# zinthesizer.net
KiCad netlist of a schematic drawn in EAGLE
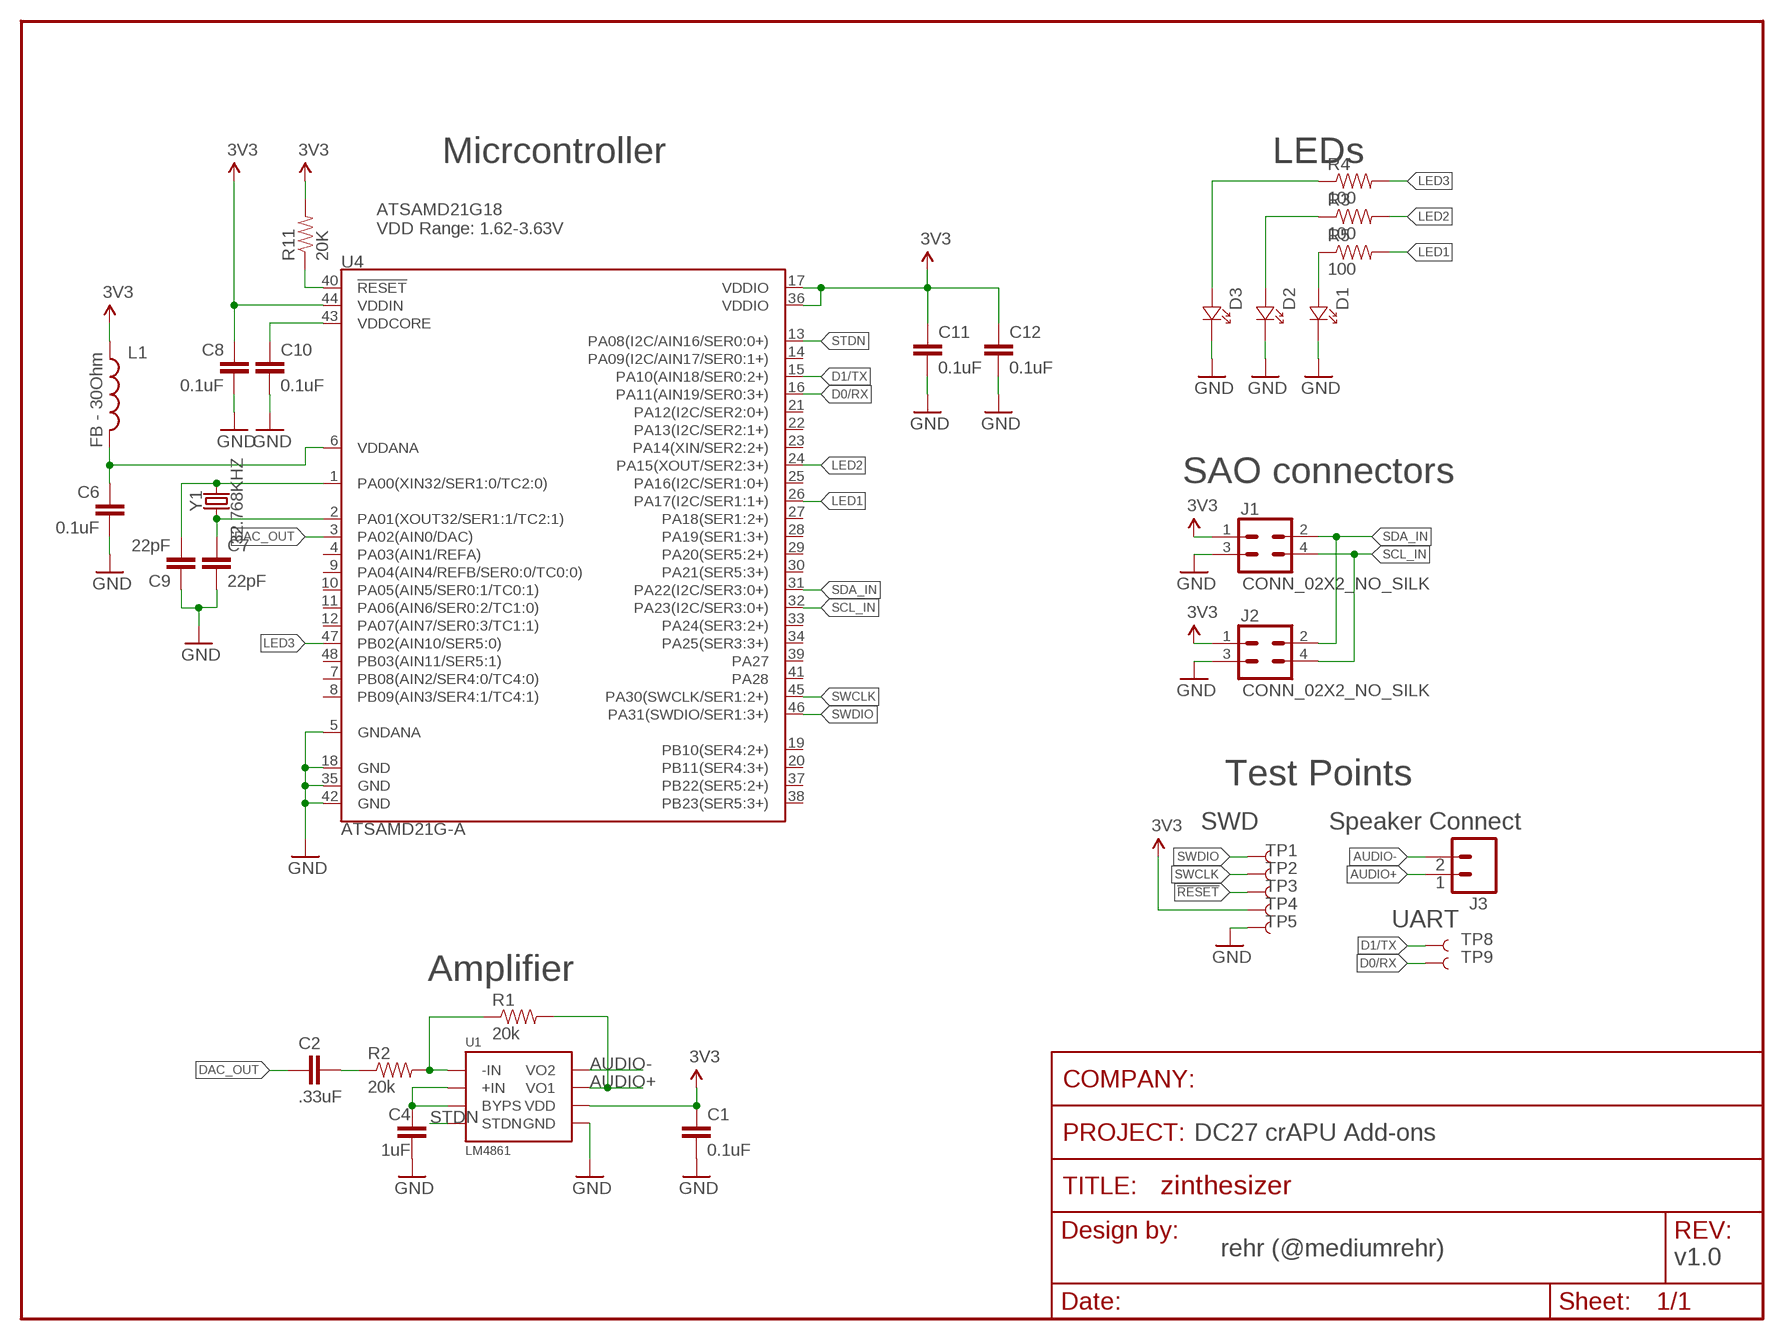
[diagram p0: schematic, sheet 1]

(export (version "E")
  (design (tool "Eeschema 10.0.6"))
  (components
    (comp (ref "C1")
      (value "0.1uF")
      (footprint "eagle-import:0603-CAP")
      (libsource (lib "eagle-import") (part "CAP0603-CAP"))
    )
    (comp (ref "C2")
      (value ".33uF")
      (footprint "eagle-import:0603-CAP")
      (libsource (lib "eagle-import") (part "CAP0603-CAP"))
    )
    (comp (ref "C4")
      (value "1uF")
      (footprint "eagle-import:0603-CAP")
      (libsource (lib "eagle-import") (part "CAP0603-CAP"))
    )
    (comp (ref "C6")
      (value "0.1uF")
      (footprint "eagle-import:0603-CAP")
      (libsource (lib "eagle-import") (part "0.1UF-25V(+80/-20%)(0603)"))
    )
    (comp (ref "C7")
      (value "22pF")
      (footprint "eagle-import:0603-CAP")
      (libsource (lib "eagle-import") (part "15PF-50V-5%(0603)"))
    )
    (comp (ref "C8")
      (value "0.1uF")
      (footprint "eagle-import:0603-CAP")
      (libsource (lib "eagle-import") (part "0.1UF-25V(+80/-20%)(0603)"))
    )
    (comp (ref "C9")
      (value "22pF")
      (footprint "eagle-import:0603-CAP")
      (libsource (lib "eagle-import") (part "15PF-50V-5%(0603)"))
    )
    (comp (ref "C10")
      (value "0.1uF")
      (footprint "eagle-import:0603-CAP")
      (libsource (lib "eagle-import") (part "0.1UF-25V(+80/-20%)(0603)"))
    )
    (comp (ref "C11")
      (value "0.1uF")
      (footprint "eagle-import:0603-CAP")
      (libsource (lib "eagle-import") (part "0.1UF-25V(+80/-20%)(0603)"))
    )
    (comp (ref "C12")
      (value "0.1uF")
      (footprint "eagle-import:0603-CAP")
      (libsource (lib "eagle-import") (part "0.1UF-25V(+80/-20%)(0603)"))
    )
    (comp (ref "D1")
      (value "LED1206REVERSE_NO_SILK")
      (footprint "eagle-import:1206_NO_SILK")
      (libsource (lib "eagle-import") (part "LED1206REVERSE_NO_SILK"))
    )
    (comp (ref "D2")
      (value "LED1206REVERSE_NO_SILK")
      (footprint "eagle-import:1206_NO_SILK")
      (libsource (lib "eagle-import") (part "LED1206REVERSE_NO_SILK"))
    )
    (comp (ref "D3")
      (value "LED1206REVERSE_NO_SILK")
      (footprint "eagle-import:1206_NO_SILK")
      (libsource (lib "eagle-import") (part "LED1206REVERSE_NO_SILK"))
    )
    (comp (ref "FRAME1")
      (value "FRAME-LETTER-BLANKNO_PACKAGE")
      (footprint "eagle-import:DUMMY")
      (fields (field (name "DESIGNER") "Nobody"))
      (libsource (lib "eagle-import") (part "FRAME-LETTER-BLANKNO_PACKAGE"))
    )
    (comp (ref "J1")
      (value "CONN_02X2_NO_SILK")
      (footprint "eagle-import:2X2_NO_SILK")
      (libsource (lib "eagle-import") (part "CONN_02X2_NO_SILK"))
    )
    (comp (ref "J2")
      (value "CONN_02X2_NO_SILK")
      (footprint "eagle-import:2X2_NO_SILK")
      (libsource (lib "eagle-import") (part "CONN_02X2_NO_SILK"))
    )
    (comp (ref "J3")
      (value "M02ROUND")
      (footprint "eagle-import:M02_ROUND")
      (libsource (lib "eagle-import") (part "M02ROUND"))
    )
    (comp (ref "L1")
      (value "FB - 30Ohm")
      (footprint "eagle-import:0603")
      (libsource (lib "eagle-import") (part "INDUCTOR0603"))
    )
    (comp (ref "R1")
      (value "20k")
      (footprint "eagle-import:0805")
      (libsource (lib "eagle-import") (part "RESISTOR0805-RES"))
    )
    (comp (ref "R2")
      (value "20k")
      (footprint "eagle-import:0805")
      (libsource (lib "eagle-import") (part "RESISTOR0805-RES"))
    )
    (comp (ref "R3")
      (value "100")
      (footprint "eagle-import:0603-RES")
      (libsource (lib "eagle-import") (part "10KOHM-1/10W-1%(0603)0603"))
    )
    (comp (ref "R4")
      (value "100")
      (footprint "eagle-import:0603-RES")
      (libsource (lib "eagle-import") (part "10KOHM-1/10W-1%(0603)0603"))
    )
    (comp (ref "R5")
      (value "100")
      (footprint "eagle-import:0603-RES")
      (libsource (lib "eagle-import") (part "10KOHM-1/10W-1%(0603)0603"))
    )
    (comp (ref "R11")
      (value "20K")
      (footprint "eagle-import:0603-RES")
      (libsource (lib "eagle-import") (part "10KOHM-1/10W-1%(0603)0603"))
    )
    (comp (ref "TP1")
      (value "TEST-POINT3X5")
      (footprint "eagle-import:PAD.03X.05")
      (libsource (lib "eagle-import") (part "TEST-POINT3X5"))
    )
    (comp (ref "TP2")
      (value "TEST-POINT3X5")
      (footprint "eagle-import:PAD.03X.05")
      (libsource (lib "eagle-import") (part "TEST-POINT3X5"))
    )
    (comp (ref "TP3")
      (value "TEST-POINT3X5")
      (footprint "eagle-import:PAD.03X.05")
      (libsource (lib "eagle-import") (part "TEST-POINT3X5"))
    )
    (comp (ref "TP4")
      (value "TEST-POINT3X5")
      (footprint "eagle-import:PAD.03X.05")
      (libsource (lib "eagle-import") (part "TEST-POINT3X5"))
    )
    (comp (ref "TP5")
      (value "TEST-POINT3X5")
      (footprint "eagle-import:PAD.03X.05")
      (libsource (lib "eagle-import") (part "TEST-POINT3X5"))
    )
    (comp (ref "TP8")
      (value "TEST-POINT3X4")
      (footprint "eagle-import:PAD.03X.04")
      (libsource (lib "eagle-import") (part "TEST-POINT3X4"))
    )
    (comp (ref "TP9")
      (value "TEST-POINT3X4")
      (footprint "eagle-import:PAD.03X.04")
      (libsource (lib "eagle-import") (part "TEST-POINT3X4"))
    )
    (comp (ref "U1")
      (value "LM4861")
      (footprint "eagle-import:8-SOIC")
      (libsource (lib "eagle-import") (part "LM4861"))
    )
    (comp (ref "U4")
      (value "ATSAMD21G-A")
      (footprint "eagle-import:TQFP-48")
      (libsource (lib "eagle-import") (part "ATSAMD21G-A"))
    )
    (comp (ref "Y1")
      (value "32.768KHZ")
      (footprint "eagle-import:ABS06")
      (libsource (lib "eagle-import") (part "ABS06-127-32.768KHZ"))
    )
  )
  (nets
    (net (code "1") (name "/~{RESET}") (class "Default")
      (node (ref "R11") (pin "1") (pinfunction "1_1") (pintype "passive"))
      (node (ref "TP3") (pin "P$1") (pinfunction "1_P$1") (pintype "bidirectional"))
      (node (ref "U4") (pin "40") (pinfunction "~{RESET}_40") (pintype "bidirectional"))
    )
    (net (code "2") (name "3V3") (class "Default")
      (node (ref "C1") (pin "1") (pinfunction "1_1") (pintype "passive"))
      (node (ref "C11") (pin "1") (pinfunction "1_1") (pintype "passive"))
      (node (ref "C12") (pin "1") (pinfunction "1_1") (pintype "passive"))
      (node (ref "C8") (pin "1") (pinfunction "1_1") (pintype "passive"))
      (node (ref "J1") (pin "1") (pinfunction "1_1") (pintype "bidirectional"))
      (node (ref "J2") (pin "1") (pinfunction "1_1") (pintype "bidirectional"))
      (node (ref "L1") (pin "1") (pinfunction "1_1") (pintype "passive"))
      (node (ref "R11") (pin "2") (pinfunction "2_2") (pintype "passive"))
      (node (ref "TP4") (pin "P$1") (pinfunction "1_P$1") (pintype "bidirectional"))
      (node (ref "U1") (pin "P$6") (pinfunction "VDD_P$6") (pintype "bidirectional"))
      (node (ref "U4") (pin "17") (pinfunction "VDDIO_17") (pintype "bidirectional"))
      (node (ref "U4") (pin "36") (pinfunction "VDDIO_36") (pintype "bidirectional"))
      (node (ref "U4") (pin "44") (pinfunction "VDDIN_44") (pintype "bidirectional"))
    )
    (net (code "3") (name "AUDIO+") (class "Default")
      (node (ref "J3") (pin "P$1") (pinfunction "P$1_P$1") (pintype "bidirectional"))
      (node (ref "R1") (pin "2") (pinfunction "2_2") (pintype "passive"))
      (node (ref "U1") (pin "P$5") (pinfunction "VO1_P$5") (pintype "bidirectional"))
    )
    (net (code "4") (name "AUDIO-") (class "Default")
      (node (ref "J3") (pin "P$2") (pinfunction "P$2_P$2") (pintype "bidirectional"))
      (node (ref "U1") (pin "P$8") (pinfunction "VO2_P$8") (pintype "bidirectional"))
    )
    (net (code "5") (name "D0{slash}RX") (class "Default")
      (node (ref "TP9") (pin "P$1") (pinfunction "1_P$1") (pintype "bidirectional"))
      (node (ref "U4") (pin "16") (pinfunction "PA11(AIN19/SER0:3+)_16") (pintype "bidirectional"))
    )
    (net (code "6") (name "D1{slash}TX") (class "Default")
      (node (ref "TP8") (pin "P$1") (pinfunction "1_P$1") (pintype "bidirectional"))
      (node (ref "U4") (pin "15") (pinfunction "PA10(AIN18/SER0:2+)_15") (pintype "bidirectional"))
    )
    (net (code "7") (name "DAC_OUT") (class "Default")
      (node (ref "C2") (pin "2") (pinfunction "2_2") (pintype "passive"))
      (node (ref "U4") (pin "3") (pinfunction "PA02(AIN0/DAC)_3") (pintype "bidirectional"))
    )
    (net (code "8") (name "GND") (class "Default")
      (node (ref "C1") (pin "2") (pinfunction "2_2") (pintype "passive"))
      (node (ref "C10") (pin "2") (pinfunction "2_2") (pintype "passive"))
      (node (ref "C11") (pin "2") (pinfunction "2_2") (pintype "passive"))
      (node (ref "C12") (pin "2") (pinfunction "2_2") (pintype "passive"))
      (node (ref "C4") (pin "2") (pinfunction "2_2") (pintype "passive"))
      (node (ref "C6") (pin "2") (pinfunction "2_2") (pintype "passive"))
      (node (ref "C7") (pin "2") (pinfunction "2_2") (pintype "passive"))
      (node (ref "C8") (pin "2") (pinfunction "2_2") (pintype "passive"))
      (node (ref "C9") (pin "1") (pinfunction "1_1") (pintype "passive"))
      (node (ref "D1") (pin "P$1") (pinfunction "P$2_P$1") (pintype "bidirectional"))
      (node (ref "D2") (pin "P$1") (pinfunction "P$2_P$1") (pintype "bidirectional"))
      (node (ref "D3") (pin "P$1") (pinfunction "P$2_P$1") (pintype "bidirectional"))
      (node (ref "J1") (pin "3") (pinfunction "3_3") (pintype "bidirectional"))
      (node (ref "J2") (pin "3") (pinfunction "3_3") (pintype "bidirectional"))
      (node (ref "TP5") (pin "P$1") (pinfunction "1_P$1") (pintype "bidirectional"))
      (node (ref "U1") (pin "P$7") (pinfunction "GND_P$7") (pintype "bidirectional"))
      (node (ref "U4") (pin "18") (pinfunction "GND_18") (pintype "bidirectional"))
      (node (ref "U4") (pin "35") (pinfunction "GND_35") (pintype "bidirectional"))
      (node (ref "U4") (pin "42") (pinfunction "GND_42") (pintype "bidirectional"))
      (node (ref "U4") (pin "5") (pinfunction "GNDANA_5") (pintype "bidirectional"))
    )
    (net (code "9") (name "LED1") (class "Default")
      (node (ref "R5") (pin "2") (pinfunction "2_2") (pintype "passive"))
      (node (ref "U4") (pin "26") (pinfunction "PA17(I2C/SER1:1+)_26") (pintype "bidirectional"))
    )
    (net (code "10") (name "LED2") (class "Default")
      (node (ref "R3") (pin "2") (pinfunction "2_2") (pintype "passive"))
      (node (ref "U4") (pin "24") (pinfunction "PA15(XOUT/SER2:3+)_24") (pintype "bidirectional"))
    )
    (net (code "11") (name "LED3") (class "Default")
      (node (ref "R4") (pin "2") (pinfunction "2_2") (pintype "passive"))
      (node (ref "U4") (pin "47") (pinfunction "PB02(AIN10/SER5:0)_47") (pintype "bidirectional"))
    )
    (net (code "12") (name "Net-(C2-Pad1)") (class "Default")
      (node (ref "C2") (pin "1") (pinfunction "1_1") (pintype "passive"))
      (node (ref "R2") (pin "1") (pinfunction "1_1") (pintype "passive"))
    )
    (net (code "13") (name "Net-(D1-P$1)") (class "Default")
      (node (ref "D1") (pin "P$2") (pinfunction "P$1_P$2") (pintype "bidirectional"))
      (node (ref "R5") (pin "1") (pinfunction "1_1") (pintype "passive"))
    )
    (net (code "14") (name "Net-(D2-P$1)") (class "Default")
      (node (ref "D2") (pin "P$2") (pinfunction "P$1_P$2") (pintype "bidirectional"))
      (node (ref "R3") (pin "1") (pinfunction "1_1") (pintype "passive"))
    )
    (net (code "15") (name "Net-(D3-P$1)") (class "Default")
      (node (ref "D3") (pin "P$2") (pinfunction "P$1_P$2") (pintype "bidirectional"))
      (node (ref "R4") (pin "1") (pinfunction "1_1") (pintype "passive"))
    )
    (net (code "16") (name "Net-(U1-+IN)") (class "Default")
      (node (ref "C4") (pin "1") (pinfunction "1_1") (pintype "passive"))
      (node (ref "U1") (pin "P$2") (pinfunction "BYPS_P$2") (pintype "bidirectional"))
      (node (ref "U1") (pin "P$3") (pinfunction "+IN_P$3") (pintype "bidirectional"))
    )
    (net (code "17") (name "Net-(U1--IN)") (class "Default")
      (node (ref "R1") (pin "1") (pinfunction "1_1") (pintype "passive"))
      (node (ref "R2") (pin "2") (pinfunction "2_2") (pintype "passive"))
      (node (ref "U1") (pin "P$4") (pinfunction "-IN_P$4") (pintype "bidirectional"))
    )
    (net (code "18") (name "Net-(U4-PA00(XIN32{slash}SER1:0{slash}TC2:0))") (class "Default")
      (node (ref "C9") (pin "2") (pinfunction "2_2") (pintype "passive"))
      (node (ref "U4") (pin "1") (pinfunction "PA00(XIN32/SER1:0/TC2:0)_1") (pintype "bidirectional"))
      (node (ref "Y1") (pin "P$2") (pinfunction "2_P$2") (pintype "passive"))
    )
    (net (code "19") (name "Net-(U4-PA01(XOUT32{slash}SER1:1{slash}TC2:1))") (class "Default")
      (node (ref "C7") (pin "1") (pinfunction "1_1") (pintype "passive"))
      (node (ref "U4") (pin "2") (pinfunction "PA01(XOUT32/SER1:1/TC2:1)_2") (pintype "bidirectional"))
      (node (ref "Y1") (pin "P$1") (pinfunction "1_P$1") (pintype "passive"))
    )
    (net (code "20") (name "Net-(U4-VDDANA)") (class "Default")
      (node (ref "C6") (pin "1") (pinfunction "1_1") (pintype "passive"))
      (node (ref "L1") (pin "2") (pinfunction "2_2") (pintype "passive"))
      (node (ref "U4") (pin "6") (pinfunction "VDDANA_6") (pintype "bidirectional"))
    )
    (net (code "21") (name "Net-(U4-VDDCORE)") (class "Default")
      (node (ref "C10") (pin "1") (pinfunction "1_1") (pintype "passive"))
      (node (ref "U4") (pin "43") (pinfunction "VDDCORE_43") (pintype "bidirectional"))
    )
    (net (code "22") (name "SCL_IN") (class "Default")
      (node (ref "J1") (pin "4") (pinfunction "4_4") (pintype "bidirectional"))
      (node (ref "J2") (pin "4") (pinfunction "4_4") (pintype "bidirectional"))
      (node (ref "U4") (pin "32") (pinfunction "PA23(I2C/SER3:0+)_32") (pintype "bidirectional"))
    )
    (net (code "23") (name "SDA_IN") (class "Default")
      (node (ref "J1") (pin "2") (pinfunction "2_2") (pintype "bidirectional"))
      (node (ref "J2") (pin "2") (pinfunction "2_2") (pintype "bidirectional"))
      (node (ref "U4") (pin "31") (pinfunction "PA22(I2C/SER3:0+)_31") (pintype "bidirectional"))
    )
    (net (code "24") (name "STDN") (class "Default")
      (node (ref "U1") (pin "P$1") (pinfunction "STDN_P$1") (pintype "bidirectional"))
      (node (ref "U4") (pin "13") (pinfunction "PA08(I2C/AIN16/SER0:0+)_13") (pintype "bidirectional"))
    )
    (net (code "25") (name "SWCLK") (class "Default")
      (node (ref "TP2") (pin "P$1") (pinfunction "1_P$1") (pintype "bidirectional"))
      (node (ref "U4") (pin "45") (pinfunction "PA30(SWCLK/SER1:2+)_45") (pintype "bidirectional"))
    )
    (net (code "26") (name "SWDIO") (class "Default")
      (node (ref "TP1") (pin "P$1") (pinfunction "1_P$1") (pintype "bidirectional"))
      (node (ref "U4") (pin "46") (pinfunction "PA31(SWDIO/SER1:3+)_46") (pintype "bidirectional"))
    )
    (net (code "27") (name "unconnected-(U4-PA03(AIN1{slash}REFA)-Pad4)") (class "Default")
      (node (ref "U4") (pin "4") (pinfunction "PA03(AIN1/REFA)_4") (pintype "bidirectional"))
    )
    (net (code "28") (name "unconnected-(U4-PA04(AIN4{slash}REFB{slash}SER0:0{slash}TC0:0)-Pad9)") (class "Default")
      (node (ref "U4") (pin "9") (pinfunction "PA04(AIN4/REFB/SER0:0/TC0:0)_9") (pintype "bidirectional"))
    )
    (net (code "29") (name "unconnected-(U4-PA05(AIN5{slash}SER0:1{slash}TC0:1)-Pad10)") (class "Default")
      (node (ref "U4") (pin "10") (pinfunction "PA05(AIN5/SER0:1/TC0:1)_10") (pintype "bidirectional"))
    )
    (net (code "30") (name "unconnected-(U4-PA06(AIN6{slash}SER0:2{slash}TC1:0)-Pad11)") (class "Default")
      (node (ref "U4") (pin "11") (pinfunction "PA06(AIN6/SER0:2/TC1:0)_11") (pintype "bidirectional"))
    )
    (net (code "31") (name "unconnected-(U4-PA07(AIN7{slash}SER0:3{slash}TC1:1)-Pad12)") (class "Default")
      (node (ref "U4") (pin "12") (pinfunction "PA07(AIN7/SER0:3/TC1:1)_12") (pintype "bidirectional"))
    )
    (net (code "32") (name "unconnected-(U4-PA09(I2C{slash}AIN17{slash}SER0:1+)-Pad14)") (class "Default")
      (node (ref "U4") (pin "14") (pinfunction "PA09(I2C/AIN17/SER0:1+)_14") (pintype "bidirectional"))
    )
    (net (code "33") (name "unconnected-(U4-PA12(I2C{slash}SER2:0+)-Pad21)") (class "Default")
      (node (ref "U4") (pin "21") (pinfunction "PA12(I2C/SER2:0+)_21") (pintype "bidirectional"))
    )
    (net (code "34") (name "unconnected-(U4-PA13(I2C{slash}SER2:1+)-Pad22)") (class "Default")
      (node (ref "U4") (pin "22") (pinfunction "PA13(I2C/SER2:1+)_22") (pintype "bidirectional"))
    )
    (net (code "35") (name "unconnected-(U4-PA14(XIN{slash}SER2:2+)-Pad23)") (class "Default")
      (node (ref "U4") (pin "23") (pinfunction "PA14(XIN/SER2:2+)_23") (pintype "bidirectional"))
    )
    (net (code "36") (name "unconnected-(U4-PA16(I2C{slash}SER1:0+)-Pad25)") (class "Default")
      (node (ref "U4") (pin "25") (pinfunction "PA16(I2C/SER1:0+)_25") (pintype "bidirectional"))
    )
    (net (code "37") (name "unconnected-(U4-PA18(SER1:2+)-Pad27)") (class "Default")
      (node (ref "U4") (pin "27") (pinfunction "PA18(SER1:2+)_27") (pintype "bidirectional"))
    )
    (net (code "38") (name "unconnected-(U4-PA19(SER1:3+)-Pad28)") (class "Default")
      (node (ref "U4") (pin "28") (pinfunction "PA19(SER1:3+)_28") (pintype "bidirectional"))
    )
    (net (code "39") (name "unconnected-(U4-PA20(SER5:2+)-Pad29)") (class "Default")
      (node (ref "U4") (pin "29") (pinfunction "PA20(SER5:2+)_29") (pintype "bidirectional"))
    )
    (net (code "40") (name "unconnected-(U4-PA21(SER5:3+)-Pad30)") (class "Default")
      (node (ref "U4") (pin "30") (pinfunction "PA21(SER5:3+)_30") (pintype "bidirectional"))
    )
    (net (code "41") (name "unconnected-(U4-PA24(SER3:2+)-Pad33)") (class "Default")
      (node (ref "U4") (pin "33") (pinfunction "PA24(SER3:2+)_33") (pintype "bidirectional"))
    )
    (net (code "42") (name "unconnected-(U4-PA25(SER3:3+)-Pad34)") (class "Default")
      (node (ref "U4") (pin "34") (pinfunction "PA25(SER3:3+)_34") (pintype "bidirectional"))
    )
    (net (code "43") (name "unconnected-(U4-PA27-Pad39)") (class "Default")
      (node (ref "U4") (pin "39") (pinfunction "PA27_39") (pintype "bidirectional"))
    )
    (net (code "44") (name "unconnected-(U4-PA28-Pad41)") (class "Default")
      (node (ref "U4") (pin "41") (pinfunction "PA28_41") (pintype "bidirectional"))
    )
    (net (code "45") (name "unconnected-(U4-PB03(AIN11{slash}SER5:1)-Pad48)") (class "Default")
      (node (ref "U4") (pin "48") (pinfunction "PB03(AIN11/SER5:1)_48") (pintype "bidirectional"))
    )
    (net (code "46") (name "unconnected-(U4-PB08(AIN2{slash}SER4:0{slash}TC4:0)-Pad7)") (class "Default")
      (node (ref "U4") (pin "7") (pinfunction "PB08(AIN2/SER4:0/TC4:0)_7") (pintype "bidirectional"))
    )
    (net (code "47") (name "unconnected-(U4-PB09(AIN3{slash}SER4:1{slash}TC4:1)-Pad8)") (class "Default")
      (node (ref "U4") (pin "8") (pinfunction "PB09(AIN3/SER4:1/TC4:1)_8") (pintype "bidirectional"))
    )
    (net (code "48") (name "unconnected-(U4-PB10(SER4:2+)-Pad19)") (class "Default")
      (node (ref "U4") (pin "19") (pinfunction "PB10(SER4:2+)_19") (pintype "bidirectional"))
    )
    (net (code "49") (name "unconnected-(U4-PB11(SER4:3+)-Pad20)") (class "Default")
      (node (ref "U4") (pin "20") (pinfunction "PB11(SER4:3+)_20") (pintype "bidirectional"))
    )
    (net (code "50") (name "unconnected-(U4-PB22(SER5:2+)-Pad37)") (class "Default")
      (node (ref "U4") (pin "37") (pinfunction "PB22(SER5:2+)_37") (pintype "bidirectional"))
    )
    (net (code "51") (name "unconnected-(U4-PB23(SER5:3+)-Pad38)") (class "Default")
      (node (ref "U4") (pin "38") (pinfunction "PB23(SER5:3+)_38") (pintype "bidirectional"))
    )
  )
)
